# Carrier_Motor_Driver.net
KiCad netlist of a schematic drawn in EAGLE
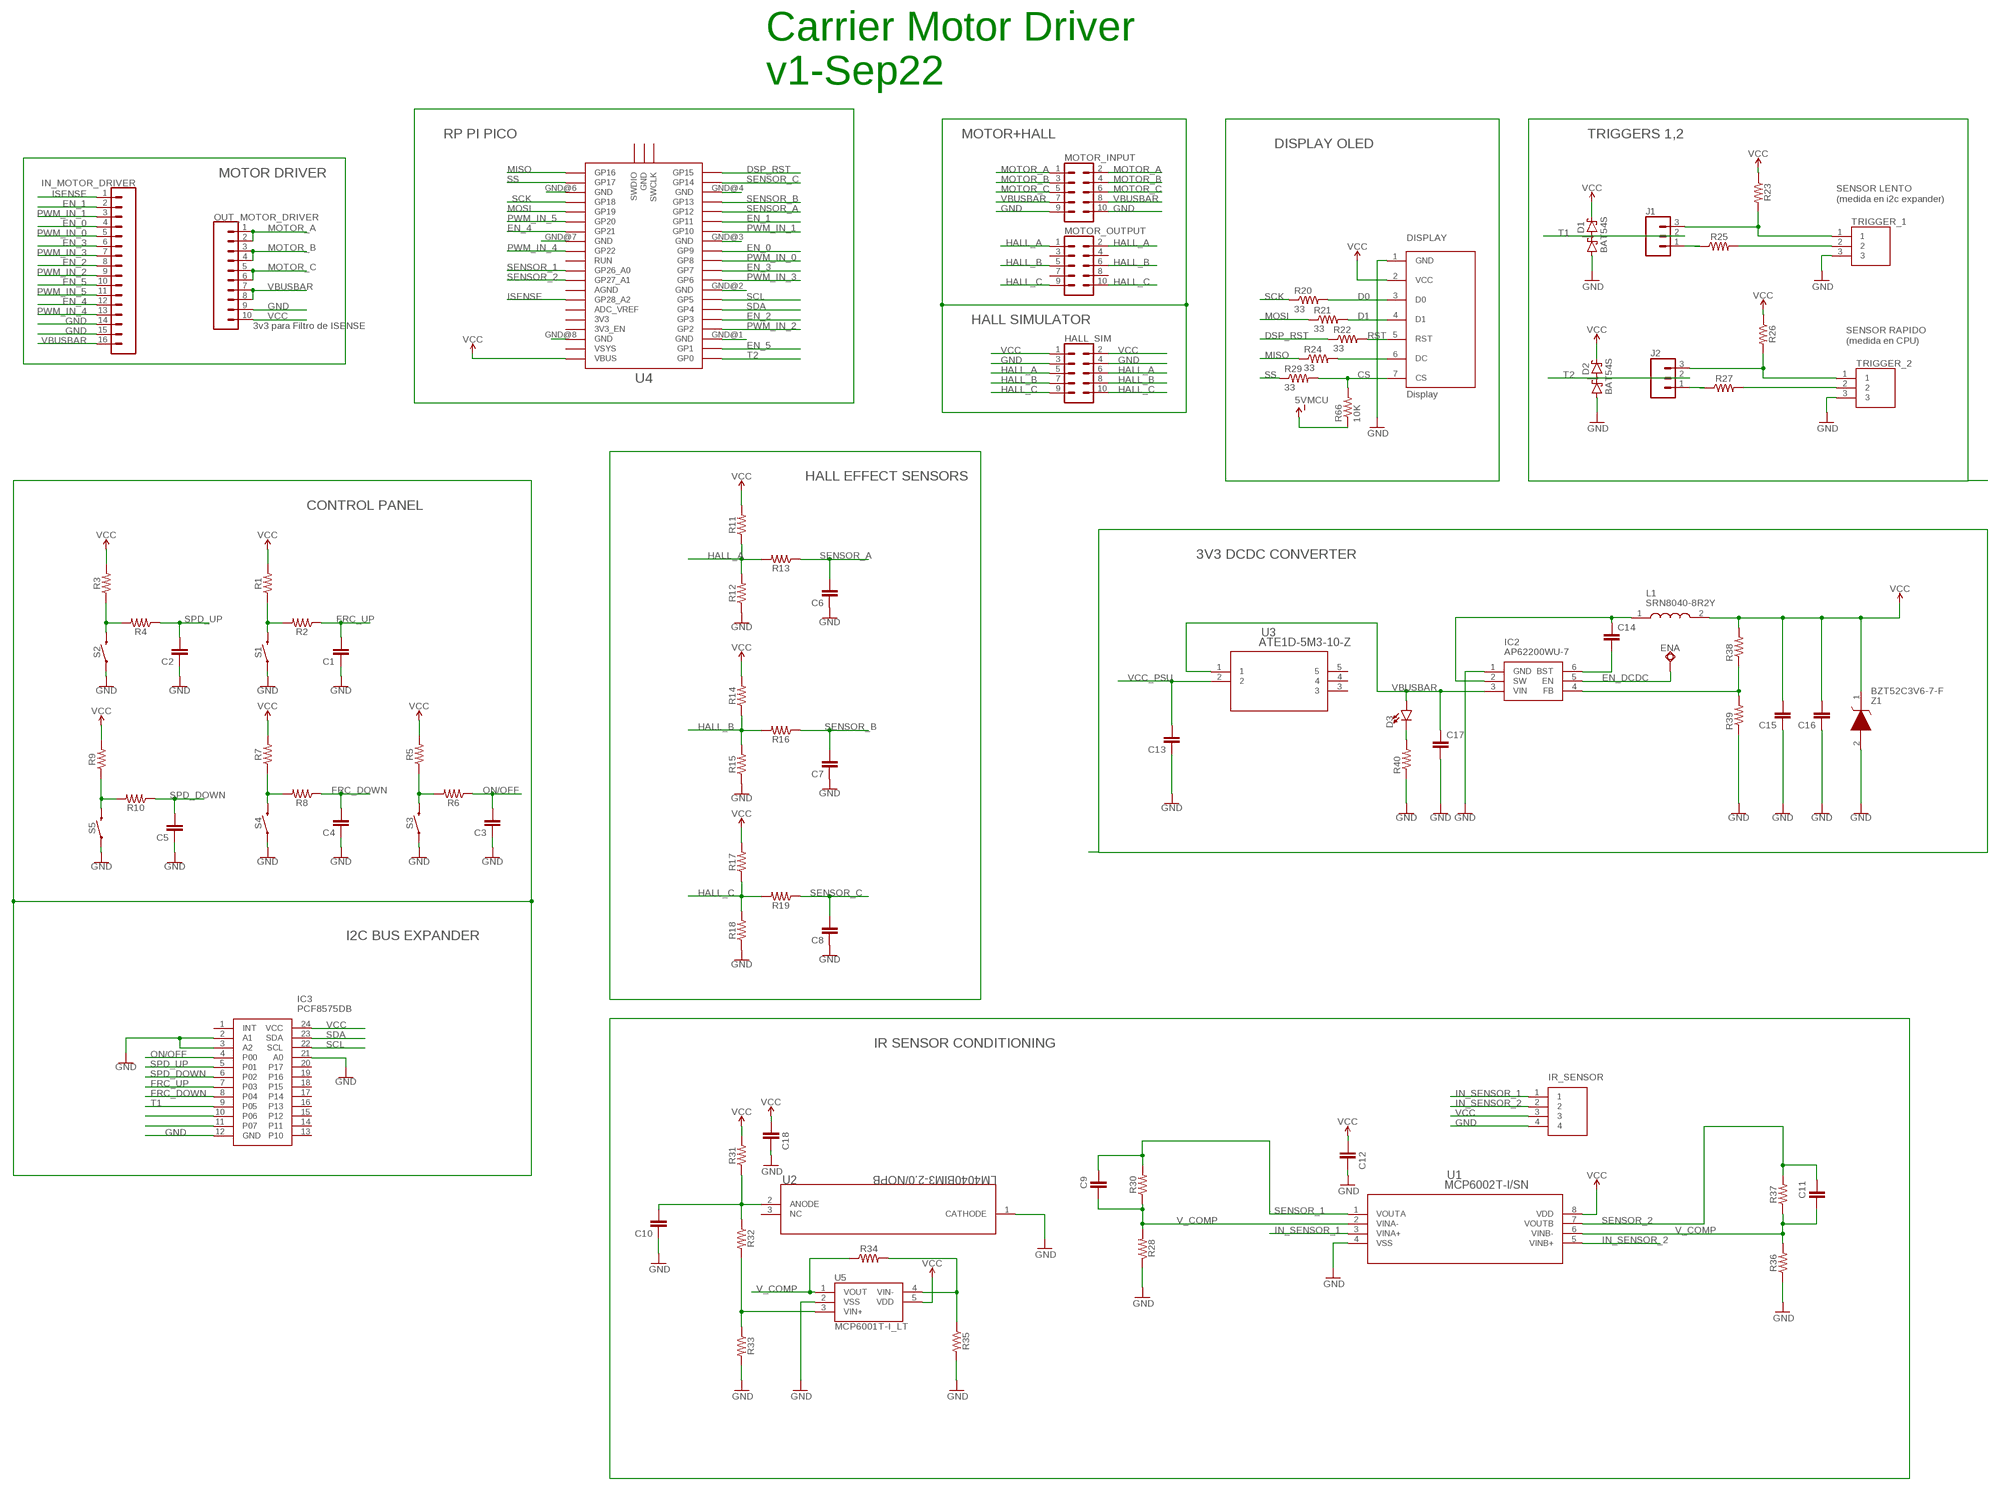
[diagram p0: schematic, sheet 1]

(export (version "E")
  (design (tool "Eeschema 10.0.6"))
  (components
    (comp (ref "C1")
      (value "C-EUC0805")
      (footprint "eagle-import:C0805")
      (libsource (lib "eagle-import") (part "C-EUC0805"))
    )
    (comp (ref "C2")
      (value "C-EUC0805")
      (footprint "eagle-import:C0805")
      (libsource (lib "eagle-import") (part "C-EUC0805"))
    )
    (comp (ref "C3")
      (value "C-EUC0805")
      (footprint "eagle-import:C0805")
      (libsource (lib "eagle-import") (part "C-EUC0805"))
    )
    (comp (ref "C4")
      (value "C-EUC0805")
      (footprint "eagle-import:C0805")
      (libsource (lib "eagle-import") (part "C-EUC0805"))
    )
    (comp (ref "C5")
      (value "C-EUC0805")
      (footprint "eagle-import:C0805")
      (libsource (lib "eagle-import") (part "C-EUC0805"))
    )
    (comp (ref "C6")
      (value "C-EUC0805")
      (footprint "eagle-import:C0805")
      (libsource (lib "eagle-import") (part "C-EUC0805"))
    )
    (comp (ref "C7")
      (value "C-EUC0805")
      (footprint "eagle-import:C0805")
      (libsource (lib "eagle-import") (part "C-EUC0805"))
    )
    (comp (ref "C8")
      (value "C-EUC0805")
      (footprint "eagle-import:C0805")
      (libsource (lib "eagle-import") (part "C-EUC0805"))
    )
    (comp (ref "C9")
      (value "C-EUC0805")
      (footprint "eagle-import:C0805")
      (libsource (lib "eagle-import") (part "C-EUC0805"))
    )
    (comp (ref "C10")
      (value "C-EUC0805")
      (footprint "eagle-import:C0805")
      (libsource (lib "eagle-import") (part "C-EUC0805"))
    )
    (comp (ref "C11")
      (value "C-EUC0805")
      (footprint "eagle-import:C0805")
      (libsource (lib "eagle-import") (part "C-EUC0805"))
    )
    (comp (ref "C12")
      (value "C-EUC0805")
      (footprint "eagle-import:C0805")
      (libsource (lib "eagle-import") (part "C-EUC0805"))
    )
    (comp (ref "C13")
      (value "C-EUC0805")
      (footprint "eagle-import:C0805")
      (libsource (lib "eagle-import") (part "C-EUC0805"))
    )
    (comp (ref "C14")
      (value "C-EUC0805")
      (footprint "eagle-import:C0805")
      (libsource (lib "eagle-import") (part "C-EUC0805"))
    )
    (comp (ref "C15")
      (value "C-EUC0805")
      (footprint "eagle-import:C0805")
      (libsource (lib "eagle-import") (part "C-EUC0805"))
    )
    (comp (ref "C16")
      (value "C-EUC0805")
      (footprint "eagle-import:C0805")
      (libsource (lib "eagle-import") (part "C-EUC0805"))
    )
    (comp (ref "C17")
      (value "C-EUC0805")
      (footprint "eagle-import:C0805")
      (libsource (lib "eagle-import") (part "C-EUC0805"))
    )
    (comp (ref "C18")
      (value "C-EUC0805")
      (footprint "eagle-import:C0805")
      (libsource (lib "eagle-import") (part "C-EUC0805"))
    )
    (comp (ref "D1")
      (value "BAT54S")
      (footprint "eagle-import:SOT23")
      (libsource (lib "eagle-import") (part "BAT54S"))
    )
    (comp (ref "D2")
      (value "BAT54S")
      (footprint "eagle-import:SOT23")
      (libsource (lib "eagle-import") (part "BAT54S"))
    )
    (comp (ref "D3")
      (value "LED3MM")
      (footprint "eagle-import:LED_3MM")
      (libsource (lib "eagle-import") (part "LED3MM"))
    )
    (comp (ref "DISPLAY")
      (value "Display")
      (footprint "eagle-import:OLED_LCD")
      (libsource (lib "eagle-import") (part "OLED_LCD"))
    )
    (comp (ref "ENA")
      (value "TESTPAD_TPSQPAD1-17")
      (footprint "eagle-import:TESTPAD_P1-17")
      (libsource (lib "eagle-import") (part "TESTPAD_TPSQPAD1-17"))
    )
    (comp (ref "HALL_SIM")
      (value "CONN_05X2NO_SILK")
      (footprint "eagle-import:2X5_NOSILK")
      (libsource (lib "eagle-import") (part "CONN_05X2NO_SILK"))
    )
    (comp (ref "IC2")
      (value "AP62200WU-7")
      (footprint "eagle-import:SOT95P280X100-6N")
      (fields (field (name "MOUSER_PART_NUMBER") "621-AP62200WU-7"))
      (libsource (lib "eagle-import") (part "AP62200WU-7"))
    )
    (comp (ref "IC3")
      (value "PCF8575DB")
      (footprint "eagle-import:SOP65P780X200-24N")
      (fields (field (name "MOUSER_PART_NUMBER") "595-PCF8575DB"))
      (libsource (lib "eagle-import") (part "PCF8575DB"))
    )
    (comp (ref "IN_MOTOR_DRIVER")
      (value "CONN_16")
      (footprint "eagle-import:1X16")
      (libsource (lib "eagle-import") (part "CONN_16"))
    )
    (comp (ref "IR_SENSOR")
      (value "OSTVN04A150")
      (footprint "eagle-import:OSTVN04A150")
      (libsource (lib "eagle-import") (part "OSTVN04A150"))
    )
    (comp (ref "J1")
      (value "CONN_03")
      (footprint "eagle-import:1X03")
      (libsource (lib "eagle-import") (part "CONN_03"))
    )
    (comp (ref "J2")
      (value "CONN_03")
      (footprint "eagle-import:1X03")
      (libsource (lib "eagle-import") (part "CONN_03"))
    )
    (comp (ref "L1")
      (value "SRN8040-8R2Y")
      (footprint "eagle-import:SRN80408R2Y")
      (fields (field (name "MOUSER_PART_NUMBER") "652-SRN8040-8R2Y"))
      (libsource (lib "eagle-import") (part "SRN8040-8R2Y"))
    )
    (comp (ref "MOTOR_INPUT")
      (value "CONN_05X2PTH")
      (footprint "eagle-import:2X5")
      (libsource (lib "eagle-import") (part "CONN_05X2PTH"))
    )
    (comp (ref "MOTOR_OUTPUT")
      (value "CONN_05X2PTH")
      (footprint "eagle-import:2X5")
      (libsource (lib "eagle-import") (part "CONN_05X2PTH"))
    )
    (comp (ref "OUT_MOTOR_DRIVER")
      (value "CONN_10\"")
      (footprint "eagle-import:1X10")
      (libsource (lib "eagle-import") (part "CONN_10{dblquote}"))
    )
    (comp (ref "R1")
      (value "RESISTOR0805")
      (footprint "eagle-import:0805")
      (libsource (lib "eagle-import") (part "RESISTOR0805"))
    )
    (comp (ref "R2")
      (value "RESISTOR0805")
      (footprint "eagle-import:0805")
      (libsource (lib "eagle-import") (part "RESISTOR0805"))
    )
    (comp (ref "R3")
      (value "RESISTOR0805")
      (footprint "eagle-import:0805")
      (libsource (lib "eagle-import") (part "RESISTOR0805"))
    )
    (comp (ref "R4")
      (value "RESISTOR0805")
      (footprint "eagle-import:0805")
      (libsource (lib "eagle-import") (part "RESISTOR0805"))
    )
    (comp (ref "R5")
      (value "RESISTOR0805")
      (footprint "eagle-import:0805")
      (libsource (lib "eagle-import") (part "RESISTOR0805"))
    )
    (comp (ref "R6")
      (value "RESISTOR0805")
      (footprint "eagle-import:0805")
      (libsource (lib "eagle-import") (part "RESISTOR0805"))
    )
    (comp (ref "R7")
      (value "RESISTOR0805")
      (footprint "eagle-import:0805")
      (libsource (lib "eagle-import") (part "RESISTOR0805"))
    )
    (comp (ref "R8")
      (value "RESISTOR0805")
      (footprint "eagle-import:0805")
      (libsource (lib "eagle-import") (part "RESISTOR0805"))
    )
    (comp (ref "R9")
      (value "RESISTOR0805")
      (footprint "eagle-import:0805")
      (libsource (lib "eagle-import") (part "RESISTOR0805"))
    )
    (comp (ref "R10")
      (value "RESISTOR0805")
      (footprint "eagle-import:0805")
      (libsource (lib "eagle-import") (part "RESISTOR0805"))
    )
    (comp (ref "R11")
      (value "RESISTOR0805")
      (footprint "eagle-import:0805")
      (libsource (lib "eagle-import") (part "RESISTOR0805"))
    )
    (comp (ref "R12")
      (value "RESISTOR0805")
      (footprint "eagle-import:0805")
      (libsource (lib "eagle-import") (part "RESISTOR0805"))
    )
    (comp (ref "R13")
      (value "RESISTOR0805")
      (footprint "eagle-import:0805")
      (libsource (lib "eagle-import") (part "RESISTOR0805"))
    )
    (comp (ref "R14")
      (value "RESISTOR0805")
      (footprint "eagle-import:0805")
      (libsource (lib "eagle-import") (part "RESISTOR0805"))
    )
    (comp (ref "R15")
      (value "RESISTOR0805")
      (footprint "eagle-import:0805")
      (libsource (lib "eagle-import") (part "RESISTOR0805"))
    )
    (comp (ref "R16")
      (value "RESISTOR0805")
      (footprint "eagle-import:0805")
      (libsource (lib "eagle-import") (part "RESISTOR0805"))
    )
    (comp (ref "R17")
      (value "RESISTOR0805")
      (footprint "eagle-import:0805")
      (libsource (lib "eagle-import") (part "RESISTOR0805"))
    )
    (comp (ref "R18")
      (value "RESISTOR0805")
      (footprint "eagle-import:0805")
      (libsource (lib "eagle-import") (part "RESISTOR0805"))
    )
    (comp (ref "R19")
      (value "RESISTOR0805")
      (footprint "eagle-import:0805")
      (libsource (lib "eagle-import") (part "RESISTOR0805"))
    )
    (comp (ref "R20")
      (value "33")
      (footprint "eagle-import:0805")
      (libsource (lib "eagle-import") (part "RESISTOR0805-RES"))
    )
    (comp (ref "R21")
      (value "33")
      (footprint "eagle-import:0805")
      (libsource (lib "eagle-import") (part "RESISTOR0805-RES"))
    )
    (comp (ref "R22")
      (value "33")
      (footprint "eagle-import:0805")
      (libsource (lib "eagle-import") (part "RESISTOR0805-RES"))
    )
    (comp (ref "R23")
      (value "RESISTOR0805")
      (footprint "eagle-import:0805")
      (libsource (lib "eagle-import") (part "RESISTOR0805"))
    )
    (comp (ref "R24")
      (value "33")
      (footprint "eagle-import:0805")
      (libsource (lib "eagle-import") (part "RESISTOR0805-RES"))
    )
    (comp (ref "R25")
      (value "RESISTOR0805")
      (footprint "eagle-import:0805")
      (libsource (lib "eagle-import") (part "RESISTOR0805"))
    )
    (comp (ref "R26")
      (value "RESISTOR0805")
      (footprint "eagle-import:0805")
      (libsource (lib "eagle-import") (part "RESISTOR0805"))
    )
    (comp (ref "R27")
      (value "RESISTOR0805")
      (footprint "eagle-import:0805")
      (libsource (lib "eagle-import") (part "RESISTOR0805"))
    )
    (comp (ref "R28")
      (value "RESISTOR0805")
      (footprint "eagle-import:0805")
      (libsource (lib "eagle-import") (part "RESISTOR0805"))
    )
    (comp (ref "R29")
      (value "33")
      (footprint "eagle-import:0805")
      (libsource (lib "eagle-import") (part "RESISTOR0805-RES"))
    )
    (comp (ref "R30")
      (value "RESISTOR0805")
      (footprint "eagle-import:0805")
      (libsource (lib "eagle-import") (part "RESISTOR0805"))
    )
    (comp (ref "R31")
      (value "RESISTOR0805")
      (footprint "eagle-import:0805")
      (libsource (lib "eagle-import") (part "RESISTOR0805"))
    )
    (comp (ref "R32")
      (value "RESISTOR0805")
      (footprint "eagle-import:0805")
      (libsource (lib "eagle-import") (part "RESISTOR0805"))
    )
    (comp (ref "R33")
      (value "RESISTOR0805")
      (footprint "eagle-import:0805")
      (libsource (lib "eagle-import") (part "RESISTOR0805"))
    )
    (comp (ref "R34")
      (value "RESISTOR0805")
      (footprint "eagle-import:0805")
      (libsource (lib "eagle-import") (part "RESISTOR0805"))
    )
    (comp (ref "R35")
      (value "RESISTOR0805")
      (footprint "eagle-import:0805")
      (libsource (lib "eagle-import") (part "RESISTOR0805"))
    )
    (comp (ref "R36")
      (value "RESISTOR0805")
      (footprint "eagle-import:0805")
      (libsource (lib "eagle-import") (part "RESISTOR0805"))
    )
    (comp (ref "R37")
      (value "RESISTOR0805")
      (footprint "eagle-import:0805")
      (libsource (lib "eagle-import") (part "RESISTOR0805"))
    )
    (comp (ref "R38")
      (value "10K")
      (footprint "eagle-import:0805")
      (libsource (lib "eagle-import") (part "RESISTOR0805-RES"))
    )
    (comp (ref "R39")
      (value "10K")
      (footprint "eagle-import:0805")
      (libsource (lib "eagle-import") (part "RESISTOR0805-RES"))
    )
    (comp (ref "R40")
      (value "10K")
      (footprint "eagle-import:0805")
      (libsource (lib "eagle-import") (part "RESISTOR0805-RES"))
    )
    (comp (ref "R66")
      (value "10K")
      (footprint "eagle-import:0805")
      (libsource (lib "eagle-import") (part "RESISTOR0805-RES"))
    )
    (comp (ref "S1")
      (value "MOMENTARY-SWITCH-SPST-SMD-5.2MM")
      (footprint "eagle-import:TACTILE_SWITCH_SMD_5.2MM")
      (libsource (lib "eagle-import") (part "MOMENTARY-SWITCH-SPST-SMD-5.2MM"))
    )
    (comp (ref "S2")
      (value "MOMENTARY-SWITCH-SPST-SMD-5.2MM")
      (footprint "eagle-import:TACTILE_SWITCH_SMD_5.2MM")
      (libsource (lib "eagle-import") (part "MOMENTARY-SWITCH-SPST-SMD-5.2MM"))
    )
    (comp (ref "S3")
      (value "MOMENTARY-SWITCH-SPST-SMD-5.2MM")
      (footprint "eagle-import:TACTILE_SWITCH_SMD_5.2MM")
      (libsource (lib "eagle-import") (part "MOMENTARY-SWITCH-SPST-SMD-5.2MM"))
    )
    (comp (ref "S4")
      (value "MOMENTARY-SWITCH-SPST-SMD-5.2MM")
      (footprint "eagle-import:TACTILE_SWITCH_SMD_5.2MM")
      (libsource (lib "eagle-import") (part "MOMENTARY-SWITCH-SPST-SMD-5.2MM"))
    )
    (comp (ref "S5")
      (value "MOMENTARY-SWITCH-SPST-SMD-5.2MM")
      (footprint "eagle-import:TACTILE_SWITCH_SMD_5.2MM")
      (libsource (lib "eagle-import") (part "MOMENTARY-SWITCH-SPST-SMD-5.2MM"))
    )
    (comp (ref "TRIGGER_1")
      (value "OSTVN03A150")
      (footprint "eagle-import:OSTVN03A150")
      (libsource (lib "eagle-import") (part "OSTVN03A150"))
    )
    (comp (ref "TRIGGER_2")
      (value "OSTVN03A150")
      (footprint "eagle-import:OSTVN03A150")
      (libsource (lib "eagle-import") (part "OSTVN03A150"))
    )
    (comp (ref "U1")
      (value "MCP6002T-I/SN")
      (footprint "eagle-import:SOIC8-N_MC_MCH")
      (fields (field (name "COPYRIGHT") "Copyright (C) 2022 Ultra Librarian. All rights reserved."))
      (libsource (lib "eagle-import") (part "MCP6002T-I/SN"))
    )
    (comp (ref "U2")
      (value "LM4040BIM3-2.0/NOPB")
      (footprint "eagle-import:DBZ3")
      (fields
        (field (name "GENERIC_PART_NUMBER") "LM4040D50")
        (field (name "MANUFACTURER") "Texas Instruments")
      )
      (libsource (lib "eagle-import") (part "LM4040BIM3-2.0/NOPB"))
    )
    (comp (ref "U3")
      (value "ATE1D-5M3-10-Z")
      (footprint "eagle-import:SPDT05_ATE1D_9P5X8_NDC")
      (fields (field (name "COPYRIGHT") "Copyright (C) 2022 Ultra Librarian. All rights reserved."))
      (libsource (lib "eagle-import") (part "ATE1D-5M3-10-Z"))
    )
    (comp (ref "U4")
      (value "RPI_PICO_IG-SMD")
      (footprint "eagle-import:RPI_PICO")
      (libsource (lib "eagle-import") (part "RPI_PICO_IG-SMD"))
    )
    (comp (ref "U5")
      (value "MCP6001T-I_LT")
      (footprint "eagle-import:SOT65P210X110-5N")
      (fields
        (field (name "ARROW_PART_NUMBER") "MCP6001T-I/LT")
        (field (name "MOUSER_PART_NUMBER") "579-MCP6001T-I/LT")
      )
      (libsource (lib "eagle-import") (part "MCP6001T-I_LT"))
    )
    (comp (ref "Z1")
      (value "BZT52C3V6-7-F")
      (footprint "eagle-import:SOD3716X135N")
      (fields (field (name "MOUSER_PART_NUMBER") "621-BZT52C3V6-F"))
      (libsource (lib "eagle-import") (part "BZT52C3V6-7-F"))
    )
  )
  (nets
    (net (code "1") (name "/CS") (class "Default")
      (node (ref "DISPLAY") (pin "7") (pinfunction "CS_7") (pintype "bidirectional"))
      (node (ref "R29") (pin "2") (pinfunction "2_2") (pintype "passive"))
      (node (ref "R66") (pin "2") (pinfunction "2_2") (pintype "passive"))
    )
    (net (code "2") (name "/D0") (class "Default")
      (node (ref "DISPLAY") (pin "3") (pinfunction "D0_3") (pintype "bidirectional"))
      (node (ref "R20") (pin "2") (pinfunction "2_2") (pintype "passive"))
    )
    (net (code "3") (name "/D1") (class "Default")
      (node (ref "DISPLAY") (pin "4") (pinfunction "D1_4") (pintype "bidirectional"))
      (node (ref "R21") (pin "2") (pinfunction "2_2") (pintype "passive"))
    )
    (net (code "4") (name "/DSP_RST") (class "Default")
      (node (ref "R22") (pin "1") (pinfunction "1_1") (pintype "passive"))
      (node (ref "U4") (pin "GP15") (pinfunction "GP15_GP15") (pintype "bidirectional"))
    )
    (net (code "5") (name "/EN_0") (class "Default")
      (node (ref "IN_MOTOR_DRIVER") (pin "4") (pinfunction "4_4") (pintype "passive"))
      (node (ref "U4") (pin "GP9") (pinfunction "GP9_GP9") (pintype "bidirectional"))
    )
    (net (code "6") (name "/EN_1") (class "Default")
      (node (ref "IN_MOTOR_DRIVER") (pin "2") (pinfunction "2_2") (pintype "passive"))
      (node (ref "U4") (pin "GP11") (pinfunction "GP11_GP11") (pintype "bidirectional"))
    )
    (net (code "7") (name "/EN_2") (class "Default")
      (node (ref "IN_MOTOR_DRIVER") (pin "8") (pinfunction "8_8") (pintype "passive"))
      (node (ref "U4") (pin "GP3") (pinfunction "GP3_GP3") (pintype "bidirectional"))
    )
    (net (code "8") (name "/EN_3") (class "Default")
      (node (ref "IN_MOTOR_DRIVER") (pin "6") (pinfunction "6_6") (pintype "passive"))
      (node (ref "U4") (pin "GP7") (pinfunction "GP7_GP7") (pintype "bidirectional"))
    )
    (net (code "9") (name "/EN_4") (class "Default")
      (node (ref "IN_MOTOR_DRIVER") (pin "12") (pinfunction "12_12") (pintype "passive"))
      (node (ref "U4") (pin "GP21") (pinfunction "GP21_GP21") (pintype "bidirectional"))
    )
    (net (code "10") (name "/EN_5") (class "Default")
      (node (ref "IN_MOTOR_DRIVER") (pin "10") (pinfunction "10_10") (pintype "passive"))
      (node (ref "U4") (pin "GP1") (pinfunction "GP1_GP1") (pintype "bidirectional"))
    )
    (net (code "11") (name "/EN_DCDC") (class "Default")
      (node (ref "ENA") (pin "TP") (pinfunction "TP_TP") (pintype "input"))
      (node (ref "IC2") (pin "5") (pinfunction "EN_5") (pintype "bidirectional"))
    )
    (net (code "12") (name "/FRC_DOWN") (class "Default")
      (node (ref "C4") (pin "2") (pinfunction "2_2") (pintype "passive"))
      (node (ref "IC3") (pin "8") (pinfunction "P04_8") (pintype "bidirectional"))
      (node (ref "R8") (pin "1") (pinfunction "1_1") (pintype "passive"))
    )
    (net (code "13") (name "/FRC_UP") (class "Default")
      (node (ref "C1") (pin "2") (pinfunction "2_2") (pintype "passive"))
      (node (ref "IC3") (pin "7") (pinfunction "P03_7") (pintype "bidirectional"))
      (node (ref "R2") (pin "1") (pinfunction "1_1") (pintype "passive"))
    )
    (net (code "14") (name "/HALL_A") (class "Default")
      (node (ref "HALL_SIM") (pin "5") (pinfunction "5_5") (pintype "passive"))
      (node (ref "HALL_SIM") (pin "6") (pinfunction "6_6") (pintype "passive"))
      (node (ref "MOTOR_OUTPUT") (pin "1") (pinfunction "1_1") (pintype "passive"))
      (node (ref "MOTOR_OUTPUT") (pin "2") (pinfunction "2_2") (pintype "passive"))
      (node (ref "R11") (pin "1") (pinfunction "1_1") (pintype "passive"))
      (node (ref "R12") (pin "2") (pinfunction "2_2") (pintype "passive"))
      (node (ref "R13") (pin "2") (pinfunction "2_2") (pintype "passive"))
    )
    (net (code "15") (name "/HALL_B") (class "Default")
      (node (ref "HALL_SIM") (pin "7") (pinfunction "7_7") (pintype "passive"))
      (node (ref "HALL_SIM") (pin "8") (pinfunction "8_8") (pintype "passive"))
      (node (ref "MOTOR_OUTPUT") (pin "5") (pinfunction "5_5") (pintype "passive"))
      (node (ref "MOTOR_OUTPUT") (pin "6") (pinfunction "6_6") (pintype "passive"))
      (node (ref "R14") (pin "1") (pinfunction "1_1") (pintype "passive"))
      (node (ref "R15") (pin "2") (pinfunction "2_2") (pintype "passive"))
      (node (ref "R16") (pin "2") (pinfunction "2_2") (pintype "passive"))
    )
    (net (code "16") (name "/HALL_C") (class "Default")
      (node (ref "HALL_SIM") (pin "10") (pinfunction "10_10") (pintype "passive"))
      (node (ref "HALL_SIM") (pin "9") (pinfunction "9_9") (pintype "passive"))
      (node (ref "MOTOR_OUTPUT") (pin "10") (pinfunction "10_10") (pintype "passive"))
      (node (ref "MOTOR_OUTPUT") (pin "9") (pinfunction "9_9") (pintype "passive"))
      (node (ref "R17") (pin "1") (pinfunction "1_1") (pintype "passive"))
      (node (ref "R18") (pin "2") (pinfunction "2_2") (pintype "passive"))
      (node (ref "R19") (pin "2") (pinfunction "2_2") (pintype "passive"))
    )
    (net (code "17") (name "/IN_SENSOR_1") (class "Default")
      (node (ref "IR_SENSOR") (pin "1") (pinfunction "1_1") (pintype "bidirectional"))
      (node (ref "U1") (pin "3") (pinfunction "VINA+_3") (pintype "input"))
    )
    (net (code "18") (name "/IN_SENSOR_2") (class "Default")
      (node (ref "IR_SENSOR") (pin "2") (pinfunction "2_2") (pintype "bidirectional"))
      (node (ref "U1") (pin "5") (pinfunction "VINB+_5") (pintype "input"))
    )
    (net (code "19") (name "/ISENSE") (class "Default")
      (node (ref "IN_MOTOR_DRIVER") (pin "1") (pinfunction "1_1") (pintype "passive"))
      (node (ref "U4") (pin "GP28_A2") (pinfunction "GP28_A2_GP28_A2") (pintype "bidirectional"))
    )
    (net (code "20") (name "/MISO") (class "Default")
      (node (ref "R24") (pin "1") (pinfunction "1_1") (pintype "passive"))
      (node (ref "U4") (pin "GP16") (pinfunction "GP16_GP16") (pintype "bidirectional"))
    )
    (net (code "21") (name "/MOSI") (class "Default")
      (node (ref "R21") (pin "1") (pinfunction "1_1") (pintype "passive"))
      (node (ref "U4") (pin "GP19") (pinfunction "GP19_GP19") (pintype "bidirectional"))
    )
    (net (code "22") (name "/MOTOR_A") (class "Default")
      (node (ref "MOTOR_INPUT") (pin "1") (pinfunction "1_1") (pintype "passive"))
      (node (ref "MOTOR_INPUT") (pin "2") (pinfunction "2_2") (pintype "passive"))
      (node (ref "OUT_MOTOR_DRIVER") (pin "1") (pinfunction "1_1") (pintype "passive"))
      (node (ref "OUT_MOTOR_DRIVER") (pin "2") (pinfunction "2_2") (pintype "passive"))
    )
    (net (code "23") (name "/MOTOR_B") (class "Default")
      (node (ref "MOTOR_INPUT") (pin "3") (pinfunction "3_3") (pintype "passive"))
      (node (ref "MOTOR_INPUT") (pin "4") (pinfunction "4_4") (pintype "passive"))
      (node (ref "OUT_MOTOR_DRIVER") (pin "3") (pinfunction "3_3") (pintype "passive"))
      (node (ref "OUT_MOTOR_DRIVER") (pin "4") (pinfunction "4_4") (pintype "passive"))
    )
    (net (code "24") (name "/MOTOR_C") (class "Default")
      (node (ref "MOTOR_INPUT") (pin "5") (pinfunction "5_5") (pintype "passive"))
      (node (ref "MOTOR_INPUT") (pin "6") (pinfunction "6_6") (pintype "passive"))
      (node (ref "OUT_MOTOR_DRIVER") (pin "5") (pinfunction "5_5") (pintype "passive"))
      (node (ref "OUT_MOTOR_DRIVER") (pin "6") (pinfunction "6_6") (pintype "passive"))
    )
    (net (code "25") (name "/ON{slash}OFF") (class "Default")
      (node (ref "C3") (pin "2") (pinfunction "2_2") (pintype "passive"))
      (node (ref "IC3") (pin "4") (pinfunction "P00_4") (pintype "bidirectional"))
      (node (ref "R6") (pin "1") (pinfunction "1_1") (pintype "passive"))
    )
    (net (code "26") (name "/PWM_IN_0") (class "Default")
      (node (ref "IN_MOTOR_DRIVER") (pin "5") (pinfunction "5_5") (pintype "passive"))
      (node (ref "U4") (pin "GP8") (pinfunction "GP8_GP8") (pintype "bidirectional"))
    )
    (net (code "27") (name "/PWM_IN_1") (class "Default")
      (node (ref "IN_MOTOR_DRIVER") (pin "3") (pinfunction "3_3") (pintype "passive"))
      (node (ref "U4") (pin "GP10") (pinfunction "GP10_GP10") (pintype "bidirectional"))
    )
    (net (code "28") (name "/PWM_IN_2") (class "Default")
      (node (ref "IN_MOTOR_DRIVER") (pin "9") (pinfunction "9_9") (pintype "passive"))
      (node (ref "U4") (pin "GP2") (pinfunction "GP2_GP2") (pintype "bidirectional"))
    )
    (net (code "29") (name "/PWM_IN_3") (class "Default")
      (node (ref "IN_MOTOR_DRIVER") (pin "7") (pinfunction "7_7") (pintype "passive"))
      (node (ref "U4") (pin "GP6") (pinfunction "GP6_GP6") (pintype "bidirectional"))
    )
    (net (code "30") (name "/PWM_IN_4") (class "Default")
      (node (ref "IN_MOTOR_DRIVER") (pin "13") (pinfunction "13_13") (pintype "passive"))
      (node (ref "U4") (pin "GP22") (pinfunction "GP22_GP22") (pintype "bidirectional"))
    )
    (net (code "31") (name "/PWM_IN_5") (class "Default")
      (node (ref "IN_MOTOR_DRIVER") (pin "11") (pinfunction "11_11") (pintype "passive"))
      (node (ref "U4") (pin "GP20") (pinfunction "GP20_GP20") (pintype "bidirectional"))
    )
    (net (code "32") (name "/RST") (class "Default")
      (node (ref "DISPLAY") (pin "5") (pinfunction "RST_5") (pintype "bidirectional"))
      (node (ref "R22") (pin "2") (pinfunction "2_2") (pintype "passive"))
    )
    (net (code "33") (name "/SCK") (class "Default")
      (node (ref "R20") (pin "1") (pinfunction "1_1") (pintype "passive"))
      (node (ref "U4") (pin "GP18") (pinfunction "GP18_GP18") (pintype "bidirectional"))
    )
    (net (code "34") (name "/SCL") (class "Default")
      (node (ref "IC3") (pin "22") (pinfunction "SCL_22") (pintype "bidirectional"))
      (node (ref "U4") (pin "GP5") (pinfunction "GP5_GP5") (pintype "bidirectional"))
    )
    (net (code "35") (name "/SDA") (class "Default")
      (node (ref "IC3") (pin "23") (pinfunction "SDA_23") (pintype "bidirectional"))
      (node (ref "U4") (pin "GP4") (pinfunction "GP4_GP4") (pintype "bidirectional"))
    )
    (net (code "36") (name "/SENSOR_1") (class "Default")
      (node (ref "C9") (pin "1") (pinfunction "1_1") (pintype "passive"))
      (node (ref "R30") (pin "2") (pinfunction "2_2") (pintype "passive"))
      (node (ref "U1") (pin "1") (pinfunction "VOUTA_1") (pintype "output"))
      (node (ref "U4") (pin "GP26_A0") (pinfunction "GP26_A0_GP26_A0") (pintype "bidirectional"))
    )
    (net (code "37") (name "/SENSOR_2") (class "Default")
      (node (ref "C11") (pin "1") (pinfunction "1_1") (pintype "passive"))
      (node (ref "R37") (pin "2") (pinfunction "2_2") (pintype "passive"))
      (node (ref "U1") (pin "7") (pinfunction "VOUTB_7") (pintype "output"))
      (node (ref "U4") (pin "GP27_A1") (pinfunction "GP27_A1_GP27_A1") (pintype "bidirectional"))
    )
    (net (code "38") (name "/SENSOR_A") (class "Default")
      (node (ref "C6") (pin "2") (pinfunction "2_2") (pintype "passive"))
      (node (ref "R13") (pin "1") (pinfunction "1_1") (pintype "passive"))
      (node (ref "U4") (pin "GP12") (pinfunction "GP12_GP12") (pintype "bidirectional"))
    )
    (net (code "39") (name "/SENSOR_B") (class "Default")
      (node (ref "C7") (pin "2") (pinfunction "2_2") (pintype "passive"))
      (node (ref "R16") (pin "1") (pinfunction "1_1") (pintype "passive"))
      (node (ref "U4") (pin "GP13") (pinfunction "GP13_GP13") (pintype "bidirectional"))
    )
    (net (code "40") (name "/SENSOR_C") (class "Default")
      (node (ref "C8") (pin "2") (pinfunction "2_2") (pintype "passive"))
      (node (ref "R19") (pin "1") (pinfunction "1_1") (pintype "passive"))
      (node (ref "U4") (pin "GP14") (pinfunction "GP14_GP14") (pintype "bidirectional"))
    )
    (net (code "41") (name "/SPD_DOWN") (class "Default")
      (node (ref "C5") (pin "2") (pinfunction "2_2") (pintype "passive"))
      (node (ref "IC3") (pin "6") (pinfunction "P02_6") (pintype "bidirectional"))
      (node (ref "R10") (pin "1") (pinfunction "1_1") (pintype "passive"))
    )
    (net (code "42") (name "/SPD_UP") (class "Default")
      (node (ref "C2") (pin "2") (pinfunction "2_2") (pintype "passive"))
      (node (ref "IC3") (pin "5") (pinfunction "P01_5") (pintype "bidirectional"))
      (node (ref "R4") (pin "1") (pinfunction "1_1") (pintype "passive"))
    )
    (net (code "43") (name "/SS") (class "Default")
      (node (ref "R29") (pin "1") (pinfunction "1_1") (pintype "passive"))
      (node (ref "U4") (pin "GP17") (pinfunction "GP17_GP17") (pintype "bidirectional"))
    )
    (net (code "44") (name "/T1") (class "Default")
      (node (ref "D1") (pin "3") (pinfunction "C1A2_3") (pintype "passive"))
      (node (ref "IC3") (pin "9") (pinfunction "P05_9") (pintype "bidirectional"))
      (node (ref "J1") (pin "2") (pinfunction "2_2") (pintype "passive"))
    )
    (net (code "45") (name "/T2") (class "Default")
      (node (ref "D2") (pin "3") (pinfunction "C1A2_3") (pintype "passive"))
      (node (ref "J2") (pin "2") (pinfunction "2_2") (pintype "passive"))
      (node (ref "U4") (pin "GP0") (pinfunction "GP0_GP0") (pintype "bidirectional"))
    )
    (net (code "46") (name "/VBUSBAR") (class "Default")
      (node (ref "C17") (pin "1") (pinfunction "1_1") (pintype "passive"))
      (node (ref "D3") (pin "A") (pinfunction "A_A") (pintype "passive"))
      (node (ref "IC2") (pin "3") (pinfunction "VIN_3") (pintype "bidirectional"))
      (node (ref "IN_MOTOR_DRIVER") (pin "16") (pinfunction "16_16") (pintype "passive"))
      (node (ref "MOTOR_INPUT") (pin "7") (pinfunction "7_7") (pintype "passive"))
      (node (ref "MOTOR_INPUT") (pin "8") (pinfunction "8_8") (pintype "passive"))
      (node (ref "OUT_MOTOR_DRIVER") (pin "7") (pinfunction "7_7") (pintype "passive"))
      (node (ref "OUT_MOTOR_DRIVER") (pin "8") (pinfunction "8_8") (pintype "passive"))
      (node (ref "U3") (pin "1") (pinfunction "1_1") (pintype "passive"))
    )
    (net (code "47") (name "/VCC_PSU") (class "Default")
      (node (ref "C13") (pin "2") (pinfunction "2_2") (pintype "passive"))
      (node (ref "U3") (pin "2") (pinfunction "2_2") (pintype "passive"))
    )
    (net (code "48") (name "/V_COMP") (class "Default")
      (node (ref "C11") (pin "2") (pinfunction "2_2") (pintype "passive"))
      (node (ref "C9") (pin "2") (pinfunction "2_2") (pintype "passive"))
      (node (ref "R28") (pin "2") (pinfunction "2_2") (pintype "passive"))
      (node (ref "R30") (pin "1") (pinfunction "1_1") (pintype "passive"))
      (node (ref "R34") (pin "1") (pinfunction "1_1") (pintype "passive"))
      (node (ref "R36") (pin "2") (pinfunction "2_2") (pintype "passive"))
      (node (ref "R37") (pin "1") (pinfunction "1_1") (pintype "passive"))
      (node (ref "U1") (pin "2") (pinfunction "VINA-_2") (pintype "input"))
      (node (ref "U1") (pin "6") (pinfunction "VINB-_6") (pintype "input"))
      (node (ref "U5") (pin "1") (pinfunction "VOUT_1") (pintype "bidirectional"))
    )
    (net (code "49") (name "5VMCU") (class "Default")
      (node (ref "R66") (pin "1") (pinfunction "1_1") (pintype "passive"))
    )
    (net (code "50") (name "GND") (class "Default")
      (node (ref "C1") (pin "1") (pinfunction "1_1") (pintype "passive"))
      (node (ref "C10") (pin "1") (pinfunction "1_1") (pintype "passive"))
      (node (ref "C12") (pin "1") (pinfunction "1_1") (pintype "passive"))
      (node (ref "C13") (pin "1") (pinfunction "1_1") (pintype "passive"))
      (node (ref "C15") (pin "1") (pinfunction "1_1") (pintype "passive"))
      (node (ref "C16") (pin "1") (pinfunction "1_1") (pintype "passive"))
      (node (ref "C17") (pin "2") (pinfunction "2_2") (pintype "passive"))
      (node (ref "C18") (pin "1") (pinfunction "1_1") (pintype "passive"))
      (node (ref "C2") (pin "1") (pinfunction "1_1") (pintype "passive"))
      (node (ref "C3") (pin "1") (pinfunction "1_1") (pintype "passive"))
      (node (ref "C4") (pin "1") (pinfunction "1_1") (pintype "passive"))
      (node (ref "C5") (pin "1") (pinfunction "1_1") (pintype "passive"))
      (node (ref "C6") (pin "1") (pinfunction "1_1") (pintype "passive"))
      (node (ref "C7") (pin "1") (pinfunction "1_1") (pintype "passive"))
      (node (ref "C8") (pin "1") (pinfunction "1_1") (pintype "passive"))
      (node (ref "D1") (pin "1") (pinfunction "A1_1") (pintype "passive"))
      (node (ref "D2") (pin "1") (pinfunction "A1_1") (pintype "passive"))
      (node (ref "DISPLAY") (pin "1") (pinfunction "GND_1") (pintype "bidirectional"))
      (node (ref "HALL_SIM") (pin "3") (pinfunction "3_3") (pintype "passive"))
      (node (ref "HALL_SIM") (pin "4") (pinfunction "4_4") (pintype "passive"))
      (node (ref "IC2") (pin "1") (pinfunction "GND_1") (pintype "bidirectional"))
      (node (ref "IC3") (pin "12") (pinfunction "GND_12") (pintype "bidirectional"))
      (node (ref "IC3") (pin "2") (pinfunction "A1_2") (pintype "bidirectional"))
      (node (ref "IC3") (pin "21") (pinfunction "A0_21") (pintype "bidirectional"))
      (node (ref "IC3") (pin "3") (pinfunction "A2_3") (pintype "bidirectional"))
      (node (ref "IN_MOTOR_DRIVER") (pin "14") (pinfunction "14_14") (pintype "passive"))
      (node (ref "IN_MOTOR_DRIVER") (pin "15") (pinfunction "15_15") (pintype "passive"))
      (node (ref "IR_SENSOR") (pin "4") (pinfunction "4_4") (pintype "bidirectional"))
      (node (ref "MOTOR_INPUT") (pin "10") (pinfunction "10_10") (pintype "passive"))
      (node (ref "MOTOR_INPUT") (pin "9") (pinfunction "9_9") (pintype "passive"))
      (node (ref "OUT_MOTOR_DRIVER") (pin "9") (pinfunction "9_9") (pintype "passive"))
      (node (ref "R12") (pin "1") (pinfunction "1_1") (pintype "passive"))
      (node (ref "R15") (pin "1") (pinfunction "1_1") (pintype "passive"))
      (node (ref "R18") (pin "1") (pinfunction "1_1") (pintype "passive"))
      (node (ref "R28") (pin "1") (pinfunction "1_1") (pintype "passive"))
      (node (ref "R33") (pin "2") (pinfunction "2_2") (pintype "passive"))
      (node (ref "R35") (pin "2") (pinfunction "2_2") (pintype "passive"))
      (node (ref "R36") (pin "1") (pinfunction "1_1") (pintype "passive"))
      (node (ref "R39") (pin "1") (pinfunction "1_1") (pintype "passive"))
      (node (ref "R40") (pin "1") (pinfunction "1_1") (pintype "passive"))
      (node (ref "S1") (pin "1") (pinfunction "1_1") (pintype "passive"))
      (node (ref "S2") (pin "1") (pinfunction "1_1") (pintype "passive"))
      (node (ref "S3") (pin "1") (pinfunction "1_1") (pintype "passive"))
      (node (ref "S4") (pin "1") (pinfunction "1_1") (pintype "passive"))
      (node (ref "S5") (pin "1") (pinfunction "1_1") (pintype "passive"))
      (node (ref "TRIGGER_1") (pin "3") (pinfunction "3_3") (pintype "bidirectional"))
      (node (ref "TRIGGER_2") (pin "3") (pinfunction "3_3") (pintype "bidirectional"))
      (node (ref "U1") (pin "4") (pinfunction "VSS_4") (pintype "passive"))
      (node (ref "U2") (pin "1") (pinfunction "CATHODE_1") (pintype "passive"))
      (node (ref "U4") (pin "GND@1") (pinfunction "GND_GND@1") (pintype "bidirectional"))
      (node (ref "U4") (pin "GND@2") (pinfunction "GND_GND@2") (pintype "bidirectional"))
      (node (ref "U4") (pin "GND@3") (pinfunction "GND_GND@3") (pintype "bidirectional"))
      (node (ref "U4") (pin "GND@4") (pinfunction "GND_GND@4") (pintype "bidirectional"))
      (node (ref "U4") (pin "GND@6") (pinfunction "GND_GND@6") (pintype "bidirectional"))
      (node (ref "U4") (pin "GND@7") (pinfunction "GND_GND@7") (pintype "bidirectional"))
      (node (ref "U4") (pin "GND@8") (pinfunction "GND_GND@8") (pintype "bidirectional"))
      (node (ref "U5") (pin "2") (pinfunction "VSS_2") (pintype "bidirectional"))
      (node (ref "Z1") (pin "2") (pinfunction "A_2") (pintype "bidirectional"))
    )
    (net (code "51") (name "Net-(D3-C)") (class "Default")
      (node (ref "D3") (pin "K") (pinfunction "C_K") (pintype "passive"))
      (node (ref "R40") (pin "2") (pinfunction "2_2") (pintype "passive"))
    )
    (net (code "52") (name "Net-(DISPLAY-DC)") (class "Default")
      (node (ref "DISPLAY") (pin "6") (pinfunction "DC_6") (pintype "bidirectional"))
      (node (ref "R24") (pin "2") (pinfunction "2_2") (pintype "passive"))
    )
    (net (code "53") (name "Net-(IC2-BST)") (class "Default")
      (node (ref "C14") (pin "2") (pinfunction "2_2") (pintype "passive"))
      (node (ref "IC2") (pin "6") (pinfunction "BST_6") (pintype "bidirectional"))
    )
    (net (code "54") (name "Net-(IC2-FB)") (class "Default")
      (node (ref "IC2") (pin "4") (pinfunction "FB_4") (pintype "bidirectional"))
      (node (ref "R38") (pin "1") (pinfunction "1_1") (pintype "passive"))
      (node (ref "R39") (pin "2") (pinfunction "2_2") (pintype "passive"))
    )
    (net (code "55") (name "Net-(IC2-SW)") (class "Default")
      (node (ref "C14") (pin "1") (pinfunction "1_1") (pintype "passive"))
      (node (ref "IC2") (pin "2") (pinfunction "SW_2") (pintype "bidirectional"))
      (node (ref "L1") (pin "1") (pinfunction "1_1") (pintype "bidirectional"))
    )
    (net (code "56") (name "Net-(J1-Pad1)") (class "Default")
      (node (ref "J1") (pin "1") (pinfunction "1_1") (pintype "passive"))
      (node (ref "R25") (pin "1") (pinfunction "1_1") (pintype "passive"))
    )
    (net (code "57") (name "Net-(J1-Pad3)") (class "Default")
      (node (ref "J1") (pin "3") (pinfunction "3_3") (pintype "passive"))
      (node (ref "R23") (pin "2") (pinfunction "2_2") (pintype "passive"))
      (node (ref "TRIGGER_1") (pin "1") (pinfunction "1_1") (pintype "bidirectional"))
    )
    (net (code "58") (name "Net-(J2-Pad1)") (class "Default")
      (node (ref "J2") (pin "1") (pinfunction "1_1") (pintype "passive"))
      (node (ref "R27") (pin "1") (pinfunction "1_1") (pintype "passive"))
    )
    (net (code "59") (name "Net-(J2-Pad3)") (class "Default")
      (node (ref "J2") (pin "3") (pinfunction "3_3") (pintype "passive"))
      (node (ref "R26") (pin "2") (pinfunction "2_2") (pintype "passive"))
      (node (ref "TRIGGER_2") (pin "1") (pinfunction "1_1") (pintype "bidirectional"))
    )
    (net (code "60") (name "Net-(R25-Pad2)") (class "Default")
      (node (ref "R25") (pin "2") (pinfunction "2_2") (pintype "passive"))
      (node (ref "TRIGGER_1") (pin "2") (pinfunction "2_2") (pintype "bidirectional"))
    )
    (net (code "61") (name "Net-(R27-Pad2)") (class "Default")
      (node (ref "R27") (pin "2") (pinfunction "2_2") (pintype "passive"))
      (node (ref "TRIGGER_2") (pin "2") (pinfunction "2_2") (pintype "bidirectional"))
    )
    (net (code "62") (name "Net-(S1-2)") (class "Default")
      (node (ref "R1") (pin "1") (pinfunction "1_1") (pintype "passive"))
      (node (ref "R2") (pin "2") (pinfunction "2_2") (pintype "passive"))
      (node (ref "S1") (pin "3") (pinfunction "2_3") (pintype "passive"))
    )
    (net (code "63") (name "Net-(S2-2)") (class "Default")
      (node (ref "R3") (pin "1") (pinfunction "1_1") (pintype "passive"))
      (node (ref "R4") (pin "2") (pinfunction "2_2") (pintype "passive"))
      (node (ref "S2") (pin "3") (pinfunction "2_3") (pintype "passive"))
    )
    (net (code "64") (name "Net-(S3-2)") (class "Default")
      (node (ref "R5") (pin "1") (pinfunction "1_1") (pintype "passive"))
      (node (ref "R6") (pin "2") (pinfunction "2_2") (pintype "passive"))
      (node (ref "S3") (pin "3") (pinfunction "2_3") (pintype "passive"))
    )
    (net (code "65") (name "Net-(S4-2)") (class "Default")
      (node (ref "R7") (pin "1") (pinfunction "1_1") (pintype "passive"))
      (node (ref "R8") (pin "2") (pinfunction "2_2") (pintype "passive"))
      (node (ref "S4") (pin "3") (pinfunction "2_3") (pintype "passive"))
    )
    (net (code "66") (name "Net-(S5-2)") (class "Default")
      (node (ref "R10") (pin "2") (pinfunction "2_2") (pintype "passive"))
      (node (ref "R9") (pin "1") (pinfunction "1_1") (pintype "passive"))
      (node (ref "S5") (pin "3") (pinfunction "2_3") (pintype "passive"))
    )
    (net (code "67") (name "Net-(U2-ANODE)") (class "Default")
      (node (ref "C10") (pin "2") (pinfunction "2_2") (pintype "passive"))
      (node (ref "R31") (pin "1") (pinfunction "1_1") (pintype "passive"))
      (node (ref "R32") (pin "1") (pinfunction "1_1") (pintype "passive"))
      (node (ref "U2") (pin "2") (pinfunction "ANODE_2") (pintype "passive"))
    )
    (net (code "68") (name "Net-(U5-VIN+)") (class "Default")
      (node (ref "R32") (pin "2") (pinfunction "2_2") (pintype "passive"))
      (node (ref "R33") (pin "1") (pinfunction "1_1") (pintype "passive"))
      (node (ref "U5") (pin "3") (pinfunction "VIN+_3") (pintype "bidirectional"))
    )
    (net (code "69") (name "Net-(U5-VIN-)") (class "Default")
      (node (ref "R34") (pin "2") (pinfunction "2_2") (pintype "passive"))
      (node (ref "R35") (pin "1") (pinfunction "1_1") (pintype "passive"))
      (node (ref "U5") (pin "4") (pinfunction "VIN-_4") (pintype "bidirectional"))
    )
    (net (code "70") (name "VCC") (class "Default")
      (node (ref "C12") (pin "2") (pinfunction "2_2") (pintype "passive"))
      (node (ref "C15") (pin "2") (pinfunction "2_2") (pintype "passive"))
      (node (ref "C16") (pin "2") (pinfunction "2_2") (pintype "passive"))
      (node (ref "C18") (pin "2") (pinfunction "2_2") (pintype "passive"))
      (node (ref "D1") (pin "2") (pinfunction "C2_2") (pintype "passive"))
      (node (ref "D2") (pin "2") (pinfunction "C2_2") (pintype "passive"))
      (node (ref "DISPLAY") (pin "2") (pinfunction "VCC_2") (pintype "bidirectional"))
      (node (ref "HALL_SIM") (pin "1") (pinfunction "1_1") (pintype "passive"))
      (node (ref "HALL_SIM") (pin "2") (pinfunction "2_2") (pintype "passive"))
      (node (ref "IC3") (pin "24") (pinfunction "VCC_24") (pintype "bidirectional"))
      (node (ref "IR_SENSOR") (pin "3") (pinfunction "3_3") (pintype "bidirectional"))
      (node (ref "L1") (pin "2") (pinfunction "2_2") (pintype "bidirectional"))
      (node (ref "OUT_MOTOR_DRIVER") (pin "10") (pinfunction "10_10") (pintype "passive"))
      (node (ref "R1") (pin "2") (pinfunction "2_2") (pintype "passive"))
      (node (ref "R11") (pin "2") (pinfunction "2_2") (pintype "passive"))
      (node (ref "R14") (pin "2") (pinfunction "2_2") (pintype "passive"))
      (node (ref "R17") (pin "2") (pinfunction "2_2") (pintype "passive"))
      (node (ref "R23") (pin "1") (pinfunction "1_1") (pintype "passive"))
      (node (ref "R26") (pin "1") (pinfunction "1_1") (pintype "passive"))
      (node (ref "R3") (pin "2") (pinfunction "2_2") (pintype "passive"))
      (node (ref "R31") (pin "2") (pinfunction "2_2") (pintype "passive"))
      (node (ref "R38") (pin "2") (pinfunction "2_2") (pintype "passive"))
      (node (ref "R5") (pin "2") (pinfunction "2_2") (pintype "passive"))
      (node (ref "R7") (pin "2") (pinfunction "2_2") (pintype "passive"))
      (node (ref "R9") (pin "2") (pinfunction "2_2") (pintype "passive"))
      (node (ref "U1") (pin "8") (pinfunction "VDD_8") (pintype "passive"))
      (node (ref "U4") (pin "VBUS") (pinfunction "VBUS_VBUS") (pintype "bidirectional"))
      (node (ref "U5") (pin "5") (pinfunction "VDD_5") (pintype "bidirectional"))
      (node (ref "Z1") (pin "1") (pinfunction "K_1") (pintype "bidirectional"))
    )
    (net (code "71") (name "unconnected-(IC3-INT-Pad1)") (class "Default")
      (node (ref "IC3") (pin "1") (pinfunction "INT_1") (pintype "bidirectional"))
    )
    (net (code "72") (name "unconnected-(IC3-P06-Pad10)") (class "Default")
      (node (ref "IC3") (pin "10") (pinfunction "P06_10") (pintype "bidirectional"))
    )
    (net (code "73") (name "unconnected-(IC3-P07-Pad11)") (class "Default")
      (node (ref "IC3") (pin "11") (pinfunction "P07_11") (pintype "bidirectional"))
    )
    (net (code "74") (name "unconnected-(IC3-P10-Pad13)") (class "Default")
      (node (ref "IC3") (pin "13") (pinfunction "P10_13") (pintype "bidirectional"))
    )
    (net (code "75") (name "unconnected-(IC3-P11-Pad14)") (class "Default")
      (node (ref "IC3") (pin "14") (pinfunction "P11_14") (pintype "bidirectional"))
    )
    (net (code "76") (name "unconnected-(IC3-P12-Pad15)") (class "Default")
      (node (ref "IC3") (pin "15") (pinfunction "P12_15") (pintype "bidirectional"))
    )
    (net (code "77") (name "unconnected-(IC3-P13-Pad16)") (class "Default")
      (node (ref "IC3") (pin "16") (pinfunction "P13_16") (pintype "bidirectional"))
    )
    (net (code "78") (name "unconnected-(IC3-P14-Pad17)") (class "Default")
      (node (ref "IC3") (pin "17") (pinfunction "P14_17") (pintype "bidirectional"))
    )
    (net (code "79") (name "unconnected-(IC3-P15-Pad18)") (class "Default")
      (node (ref "IC3") (pin "18") (pinfunction "P15_18") (pintype "bidirectional"))
    )
    (net (code "80") (name "unconnected-(IC3-P16-Pad19)") (class "Default")
      (node (ref "IC3") (pin "19") (pinfunction "P16_19") (pintype "bidirectional"))
    )
    (net (code "81") (name "unconnected-(IC3-P17-Pad20)") (class "Default")
      (node (ref "IC3") (pin "20") (pinfunction "P17_20") (pintype "bidirectional"))
    )
    (net (code "82") (name "unconnected-(MOTOR_OUTPUT-Pad3)") (class "Default")
      (node (ref "MOTOR_OUTPUT") (pin "3") (pinfunction "3_3") (pintype "passive"))
    )
    (net (code "83") (name "unconnected-(MOTOR_OUTPUT-Pad4)") (class "Default")
      (node (ref "MOTOR_OUTPUT") (pin "4") (pinfunction "4_4") (pintype "passive"))
    )
    (net (code "84") (name "unconnected-(MOTOR_OUTPUT-Pad7)") (class "Default")
      (node (ref "MOTOR_OUTPUT") (pin "7") (pinfunction "7_7") (pintype "passive"))
    )
    (net (code "85") (name "unconnected-(MOTOR_OUTPUT-Pad8)") (class "Default")
      (node (ref "MOTOR_OUTPUT") (pin "8") (pinfunction "8_8") (pintype "passive"))
    )
    (net (code "86") (name "unconnected-(U2-NC-Pad3)") (class "Default")
      (node (ref "U2") (pin "3") (pinfunction "NC_3") (pintype "passive"))
    )
    (net (code "87") (name "unconnected-(U3-Pad3)") (class "Default")
      (node (ref "U3") (pin "3") (pinfunction "3_3") (pintype "passive"))
    )
    (net (code "88") (name "unconnected-(U3-Pad4)") (class "Default")
      (node (ref "U3") (pin "4") (pinfunction "4_4") (pintype "passive"))
    )
    (net (code "89") (name "unconnected-(U3-Pad5)") (class "Default")
      (node (ref "U3") (pin "5") (pinfunction "5_5") (pintype "passive"))
    )
    (net (code "90") (name "unconnected-(U4-GND-PadGND@5)") (class "Default")
      (node (ref "U4") (pin "GND@5") (pinfunction "GND_GND@5") (pintype "bidirectional"))
    )
    (net (code "91") (name "unconnected-(U4-Pad3V3)") (class "Default")
      (node (ref "U4") (pin "3V3") (pinfunction "3V3_3V3") (pintype "bidirectional"))
    )
    (net (code "92") (name "unconnected-(U4-Pad3V3_EN)") (class "Default")
      (node (ref "U4") (pin "3V3_EN") (pinfunction "3V3_EN_3V3_EN") (pintype "bidirectional"))
    )
    (net (code "93") (name "unconnected-(U4-PadADC_VREF)") (class "Default")
      (node (ref "U4") (pin "ADC_VREF") (pinfunction "ADC_VREF_ADC_VREF") (pintype "bidirectional"))
    )
    (net (code "94") (name "unconnected-(U4-PadAGND)") (class "Default")
      (node (ref "U4") (pin "AGND") (pinfunction "AGND_AGND") (pintype "bidirectional"))
    )
    (net (code "95") (name "unconnected-(U4-PadRUN)") (class "Default")
      (node (ref "U4") (pin "RUN") (pinfunction "RUN_RUN") (pintype "bidirectional"))
    )
    (net (code "96") (name "unconnected-(U4-PadSWCLK)") (class "Default")
      (node (ref "U4") (pin "SWCLK") (pinfunction "SWCLK_SWCLK") (pintype "bidirectional"))
    )
    (net (code "97") (name "unconnected-(U4-PadSWDIO)") (class "Default")
      (node (ref "U4") (pin "SWDIO") (pinfunction "SWDIO_SWDIO") (pintype "bidirectional"))
    )
    (net (code "98") (name "unconnected-(U4-PadVSYS)") (class "Default")
      (node (ref "U4") (pin "VSYS") (pinfunction "VSYS_VSYS") (pintype "bidirectional"))
    )
  )
)
